# Duty_cycle_BDD_1.net
KiCad netlist of a schematic drawn in Altium Designer
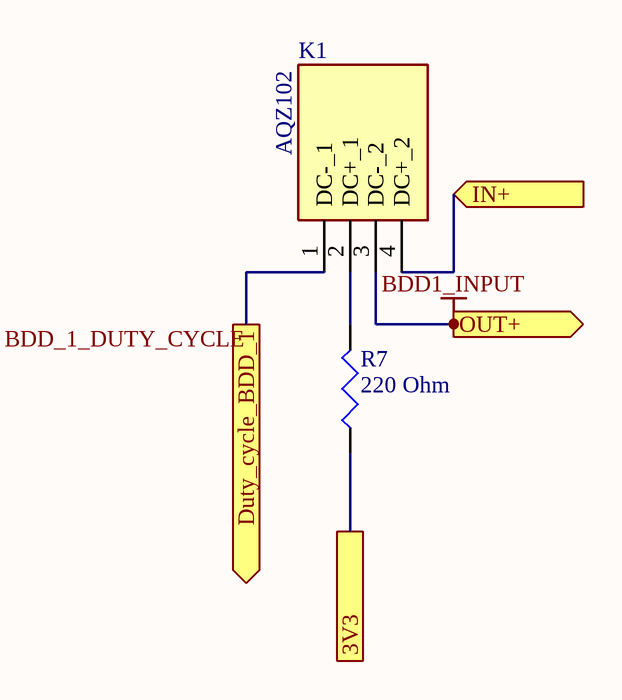
[diagram p0: Duty_cycle_BDD_1.SchDoc]

(export (version "E")
  (design (tool "Eeschema 10.0.6"))
  (components
    (comp (ref "K1")
      (value "AQZ102")
      (footprint "SamacSys:AQZ102")
      (description "Relay or Contactor")
      (fields (field (name "MOUSER PART NUMBER") "769-AQZ102"))
      (libsource (lib "*") (part "AQZ102"))
    )
    (comp (ref "R7")
      (value "220 Ohm")
      (footprint "J1-0603")
      (description "Resistor")
      (fields (field (name "PUBLISHER") "Altium Limited"))
      (libsource (lib "Miscellaneous Devices") (part "Res3"))
    )
  )
  (nets
    (net (code "1") (name "/3V3") (class "Default")
      (node (ref "R7") (pin "1") (pinfunction "1_1") (pintype "passive"))
    )
    (net (code "2") (name "/BDD_1_DUTY_CYCLE") (class "Default")
      (node (ref "K1") (pin "1") (pinfunction "DC-_1_1") (pintype "passive"))
    )
    (net (code "3") (name "/IN+") (class "Default")
      (node (ref "K1") (pin "4") (pinfunction "DC+_2_4") (pintype "passive"))
    )
    (net (code "4") (name "BDD1_INPUT") (class "Default")
      (node (ref "K1") (pin "3") (pinfunction "DC-_2_3") (pintype "passive"))
    )
    (net (code "5") (name "Net-(K1-DC+_1)") (class "Default")
      (node (ref "K1") (pin "2") (pinfunction "DC+_1_2") (pintype "passive"))
      (node (ref "R7") (pin "2") (pinfunction "2_2") (pintype "passive"))
    )
  )
)
